# riffle-CTL-0_2.net
KiCad netlist of a schematic drawn in EAGLE
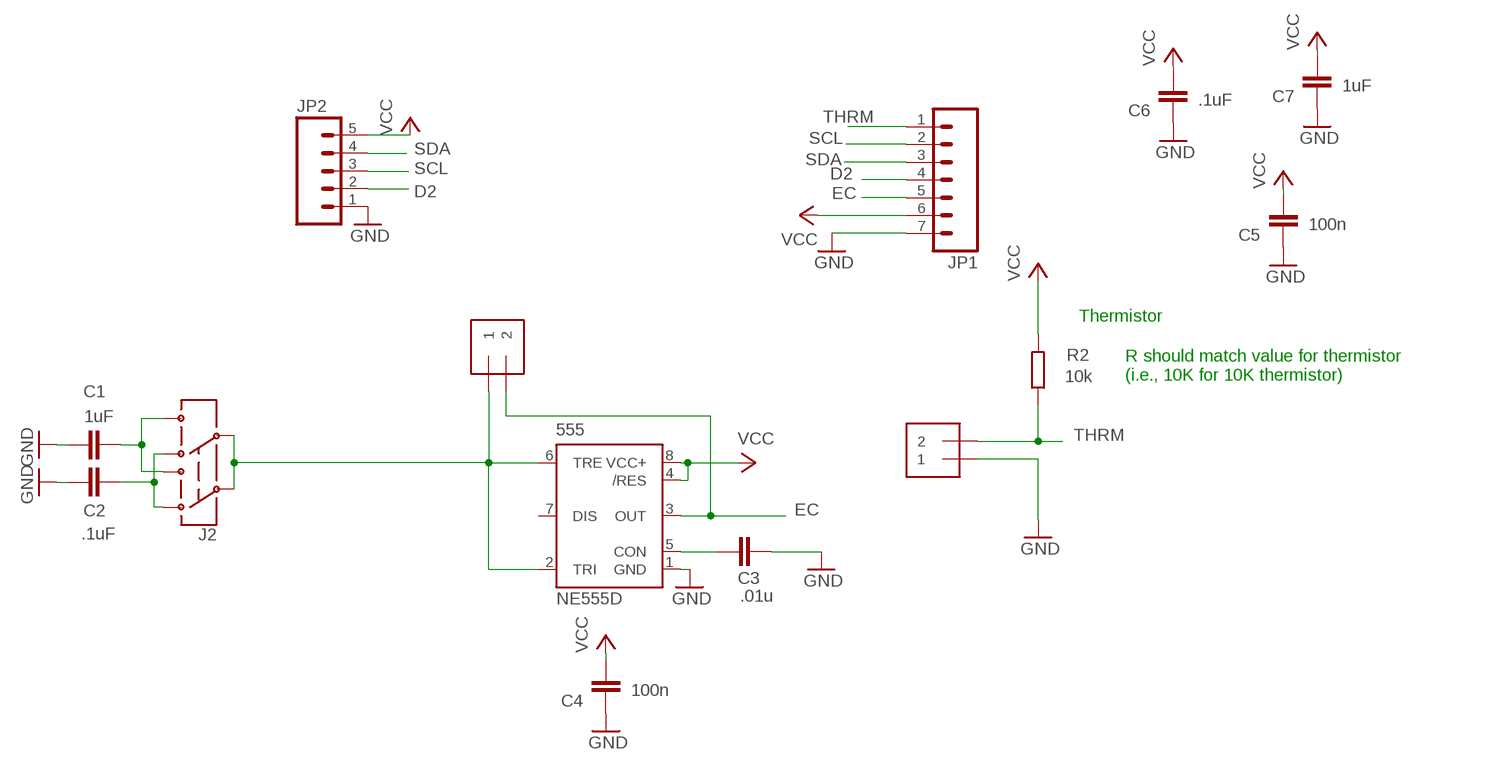
[diagram p0: schematic, sheet 1]

(export (version "E")
  (design (tool "Eeschema 10.0.6"))
  (components
    (comp (ref "555")
      (value "NE555D")
      (footprint "eagle-import:SO08@1")
      (libsource (lib "eagle-import") (part "NE555D"))
    )
    (comp (ref "C1")
      (value "1uF")
      (footprint "eagle-import:C0805")
      (libsource (lib "eagle-import") (part "C-EUC0805"))
    )
    (comp (ref "C2")
      (value ".1uF")
      (footprint "eagle-import:C0805")
      (libsource (lib "eagle-import") (part "C-EUC0805"))
    )
    (comp (ref "C3")
      (value ".01u")
      (footprint "eagle-import:C0805")
      (libsource (lib "eagle-import") (part "C-EUC0805"))
    )
    (comp (ref "C4")
      (value "100n")
      (footprint "eagle-import:C0805")
      (libsource (lib "eagle-import") (part "C-EUC0805"))
    )
    (comp (ref "C5")
      (value "100n")
      (footprint "eagle-import:C0805")
      (libsource (lib "eagle-import") (part "C-EUC0805"))
    )
    (comp (ref "C6")
      (value ".1uF")
      (footprint "eagle-import:C0805")
      (libsource (lib "eagle-import") (part "C-EUC0805"))
    )
    (comp (ref "C7")
      (value "1uF")
      (footprint "eagle-import:C0805")
      (libsource (lib "eagle-import") (part "C-EUC0805"))
    )
    (comp (ref "EC")
      (value "1X2-3.5MM")
      (footprint "eagle-import:1X2-3.5MM")
      (libsource (lib "eagle-import") (part "1X2-3.5MM"))
    )
    (comp (ref "J2")
      (value "AYZ0202")
      (footprint "eagle-import:AYZ0202")
      (libsource (lib "eagle-import") (part "AYZ0202"))
    )
    (comp (ref "JP1")
      (value "M07")
      (footprint "eagle-import:1X07")
      (libsource (lib "eagle-import") (part "M07"))
    )
    (comp (ref "JP2")
      (value "M05PTH")
      (footprint "eagle-import:1X05")
      (libsource (lib "eagle-import") (part "M05PTH"))
    )
    (comp (ref "R2")
      (value "10k")
      (footprint "eagle-import:R0805")
      (libsource (lib "eagle-import") (part "R-EU_R0805"))
    )
    (comp (ref "THRM")
      (value "1X2-3.5MM")
      (footprint "eagle-import:1X2-3.5MM")
      (libsource (lib "eagle-import") (part "1X2-3.5MM"))
    )
  )
  (nets
    (net (code "1") (name "/D2") (class "Default")
      (node (ref "JP1") (pin "4") (pinfunction "4_4") (pintype "passive"))
      (node (ref "JP2") (pin "2") (pinfunction "2_2") (pintype "passive"))
    )
    (net (code "2") (name "/EC") (class "Default")
      (node (ref "555") (pin "3") (pinfunction "OUT_3") (pintype "output"))
      (node (ref "EC") (pin "2") (pinfunction "2_2") (pintype "passive"))
      (node (ref "JP1") (pin "5") (pinfunction "5_5") (pintype "passive"))
    )
    (net (code "3") (name "/SCL") (class "Default")
      (node (ref "JP1") (pin "2") (pinfunction "2_2") (pintype "passive"))
      (node (ref "JP2") (pin "3") (pinfunction "3_3") (pintype "passive"))
    )
    (net (code "4") (name "/SDA") (class "Default")
      (node (ref "JP1") (pin "3") (pinfunction "3_3") (pintype "passive"))
      (node (ref "JP2") (pin "4") (pinfunction "4_4") (pintype "passive"))
    )
    (net (code "5") (name "/THRM") (class "Default")
      (node (ref "JP1") (pin "1") (pinfunction "1_1") (pintype "passive"))
      (node (ref "R2") (pin "1") (pinfunction "1_1") (pintype "passive"))
      (node (ref "THRM") (pin "2") (pinfunction "2_2") (pintype "passive"))
    )
    (net (code "6") (name "GND") (class "Default")
      (node (ref "555") (pin "1") (pinfunction "GND_1") (pintype "power_in"))
      (node (ref "C1") (pin "2") (pinfunction "2_2") (pintype "passive"))
      (node (ref "C2") (pin "2") (pinfunction "2_2") (pintype "passive"))
      (node (ref "C3") (pin "1") (pinfunction "1_1") (pintype "passive"))
      (node (ref "C4") (pin "1") (pinfunction "1_1") (pintype "passive"))
      (node (ref "C5") (pin "1") (pinfunction "1_1") (pintype "passive"))
      (node (ref "C6") (pin "1") (pinfunction "1_1") (pintype "passive"))
      (node (ref "C7") (pin "1") (pinfunction "1_1") (pintype "passive"))
      (node (ref "JP1") (pin "7") (pinfunction "7_7") (pintype "passive"))
      (node (ref "JP2") (pin "1") (pinfunction "1_1") (pintype "passive"))
      (node (ref "THRM") (pin "1") (pinfunction "1_1") (pintype "passive"))
    )
    (net (code "7") (name "Net-(555-CON)") (class "Default")
      (node (ref "555") (pin "5") (pinfunction "CON_5") (pintype "input"))
      (node (ref "C3") (pin "2") (pinfunction "2_2") (pintype "passive"))
    )
    (net (code "8") (name "Net-(555-TRE)") (class "Default")
      (node (ref "555") (pin "2") (pinfunction "TRI_2") (pintype "input"))
      (node (ref "555") (pin "6") (pinfunction "TRE_6") (pintype "input"))
      (node (ref "EC") (pin "1") (pinfunction "1_1") (pintype "passive"))
      (node (ref "J2") (pin "2") (pinfunction "2_2") (pintype "bidirectional"))
      (node (ref "J2") (pin "5") (pinfunction "5_5") (pintype "bidirectional"))
    )
    (net (code "9") (name "Net-(J2-1)") (class "Default")
      (node (ref "C2") (pin "1") (pinfunction "1_1") (pintype "passive"))
      (node (ref "J2") (pin "3") (pinfunction "1_3") (pintype "bidirectional"))
      (node (ref "J2") (pin "6") (pinfunction "4_6") (pintype "bidirectional"))
    )
    (net (code "10") (name "Net-(J2-3)") (class "Default")
      (node (ref "C1") (pin "1") (pinfunction "1_1") (pintype "passive"))
      (node (ref "J2") (pin "1") (pinfunction "3_1") (pintype "bidirectional"))
      (node (ref "J2") (pin "4") (pinfunction "6_4") (pintype "bidirectional"))
    )
    (net (code "11") (name "VCC") (class "Default")
      (node (ref "555") (pin "4") (pinfunction "/RES_4") (pintype "input"))
      (node (ref "555") (pin "8") (pinfunction "VCC+_8") (pintype "power_in"))
      (node (ref "C4") (pin "2") (pinfunction "2_2") (pintype "passive"))
      (node (ref "C5") (pin "2") (pinfunction "2_2") (pintype "passive"))
      (node (ref "C6") (pin "2") (pinfunction "2_2") (pintype "passive"))
      (node (ref "C7") (pin "2") (pinfunction "2_2") (pintype "passive"))
      (node (ref "JP1") (pin "6") (pinfunction "6_6") (pintype "passive"))
      (node (ref "JP2") (pin "5") (pinfunction "5_5") (pintype "passive"))
      (node (ref "R2") (pin "2") (pinfunction "2_2") (pintype "passive"))
    )
    (net (code "12") (name "unconnected-(555-DIS-Pad7)") (class "Default")
      (node (ref "555") (pin "7") (pinfunction "DIS_7") (pintype "input"))
    )
  )
)
